# TT7D_v1_0.net
KiCad netlist of a schematic drawn in EAGLE
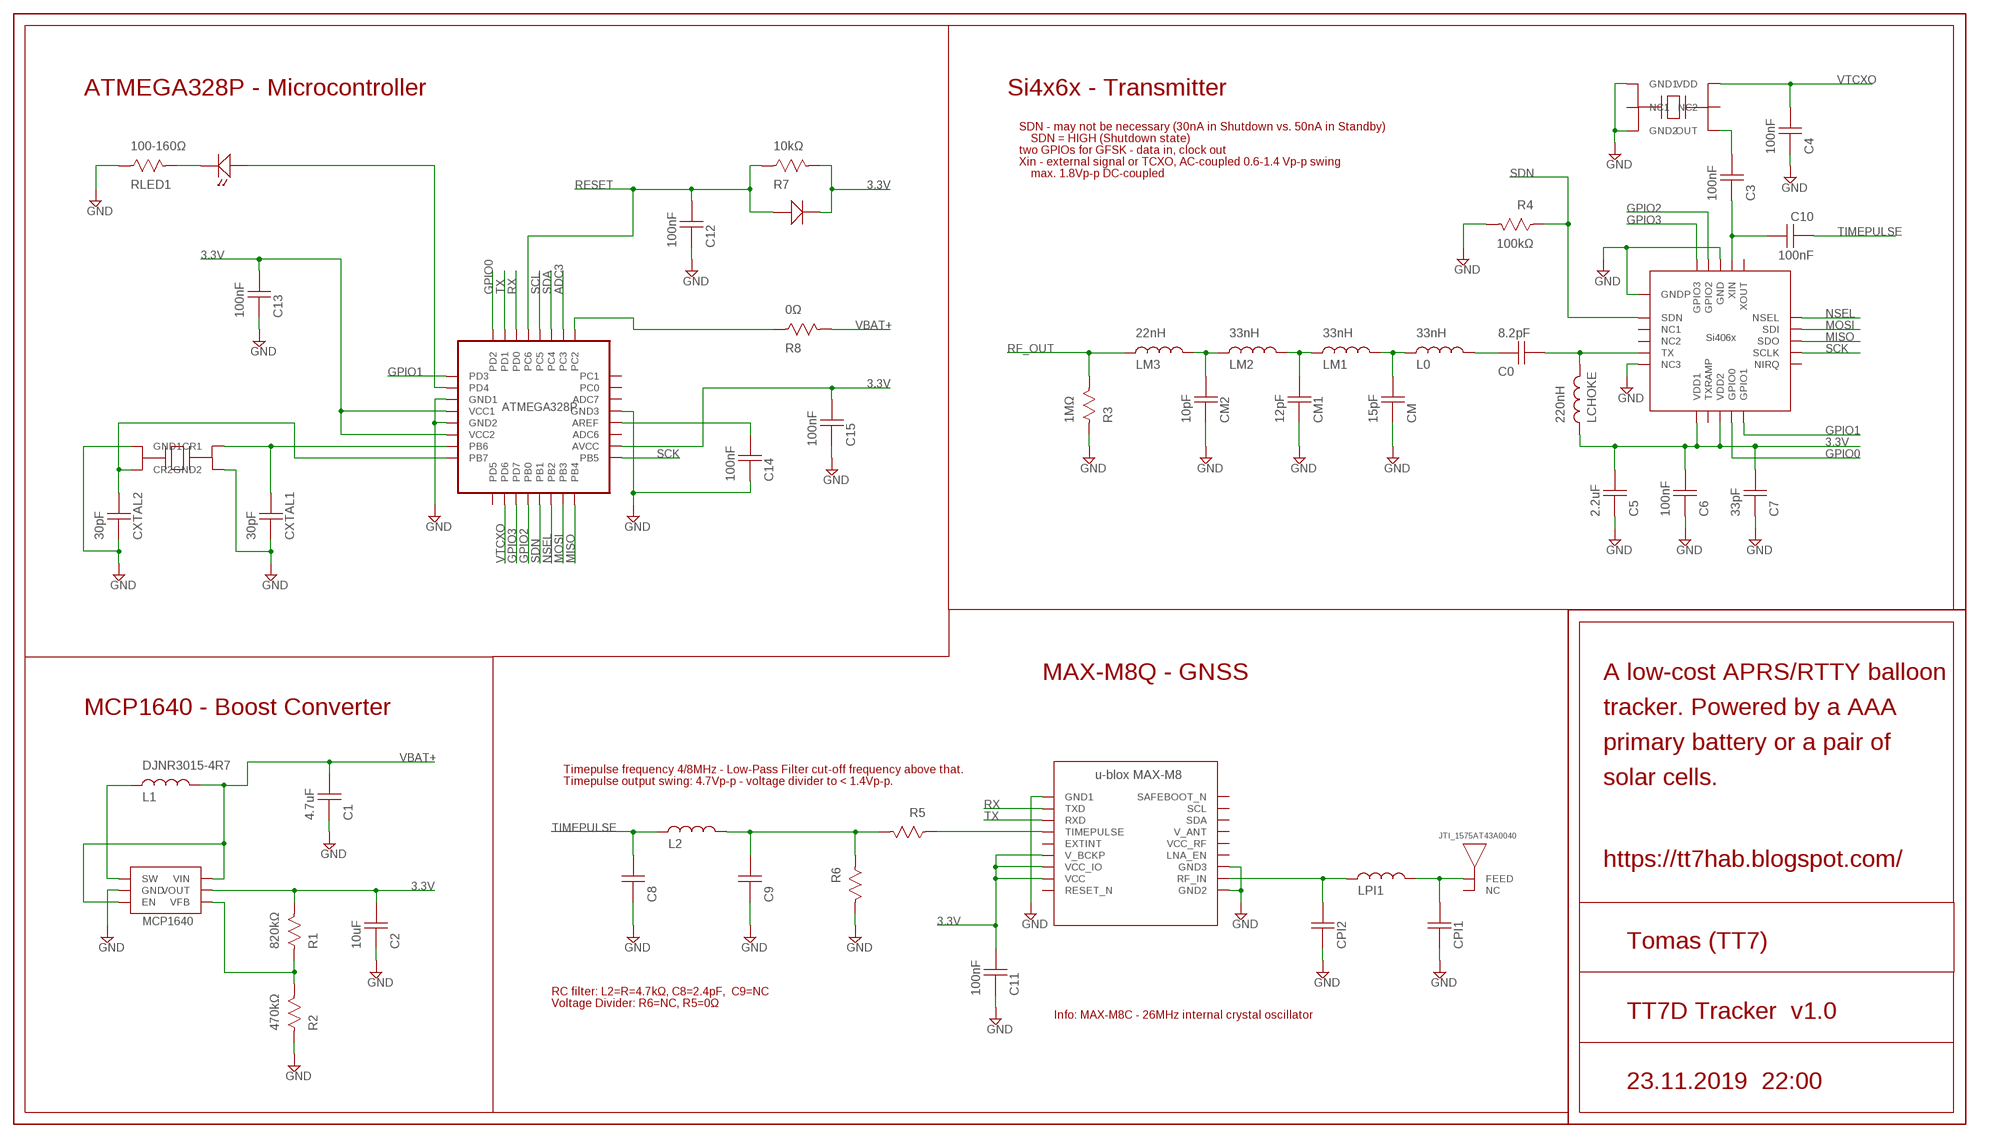
[diagram p0: schematic, sheet 1]

(export (version "E")
  (design (tool "Eeschema 10.0.6"))
  (components
    (comp (ref "ANT1")
      (value "JTI_1575AT43A0040")
      (footprint "eagle-import:JTI_1575AT43A0040")
      (libsource (lib "eagle-import") (part "JTI_1575AT43A0040"))
    )
    (comp (ref "C0")
      (value "8.2pF")
      (footprint "eagle-import:CAP0402")
      (libsource (lib "eagle-import") (part "CAP0402"))
    )
    (comp (ref "C1")
      (value "4.7uF")
      (footprint "eagle-import:CAP0402")
      (libsource (lib "eagle-import") (part "CAP0402"))
    )
    (comp (ref "C2")
      (value "10uF")
      (footprint "eagle-import:CAP0402")
      (libsource (lib "eagle-import") (part "CAP0402"))
    )
    (comp (ref "C3")
      (value "100nF")
      (footprint "eagle-import:CAP0402")
      (libsource (lib "eagle-import") (part "CAP0402"))
    )
    (comp (ref "C4")
      (value "100nF")
      (footprint "eagle-import:CAP0402")
      (libsource (lib "eagle-import") (part "CAP0402"))
    )
    (comp (ref "C5")
      (value "2.2uF")
      (footprint "eagle-import:CAP0402")
      (libsource (lib "eagle-import") (part "CAP0402"))
    )
    (comp (ref "C6")
      (value "100nF")
      (footprint "eagle-import:CAP0402")
      (libsource (lib "eagle-import") (part "CAP0402"))
    )
    (comp (ref "C7")
      (value "33pF")
      (footprint "eagle-import:CAP0402")
      (libsource (lib "eagle-import") (part "CAP0402"))
    )
    (comp (ref "C8")
      (value "CAP0402")
      (footprint "eagle-import:CAP0402")
      (libsource (lib "eagle-import") (part "CAP0402"))
    )
    (comp (ref "C9")
      (value "CAP0402")
      (footprint "eagle-import:CAP0402")
      (libsource (lib "eagle-import") (part "CAP0402"))
    )
    (comp (ref "C10")
      (value "100nF")
      (footprint "eagle-import:CAP0402")
      (libsource (lib "eagle-import") (part "CAP0402"))
    )
    (comp (ref "C11")
      (value "100nF")
      (footprint "eagle-import:CAP0402")
      (libsource (lib "eagle-import") (part "CAP0402"))
    )
    (comp (ref "C12")
      (value "100nF")
      (footprint "eagle-import:CAP0402")
      (libsource (lib "eagle-import") (part "CAP0402"))
    )
    (comp (ref "C13")
      (value "100nF")
      (footprint "eagle-import:CAP0402")
      (libsource (lib "eagle-import") (part "CAP0402"))
    )
    (comp (ref "C14")
      (value "100nF")
      (footprint "eagle-import:CAP0402")
      (libsource (lib "eagle-import") (part "CAP0402"))
    )
    (comp (ref "C15")
      (value "100nF")
      (footprint "eagle-import:CAP0402")
      (libsource (lib "eagle-import") (part "CAP0402"))
    )
    (comp (ref "CM")
      (value "15pF")
      (footprint "eagle-import:CAP0402")
      (libsource (lib "eagle-import") (part "CAP0402"))
    )
    (comp (ref "CM1")
      (value "12pF")
      (footprint "eagle-import:CAP0402")
      (libsource (lib "eagle-import") (part "CAP0402"))
    )
    (comp (ref "CM2")
      (value "10pF")
      (footprint "eagle-import:CAP0402")
      (libsource (lib "eagle-import") (part "CAP0402"))
    )
    (comp (ref "CPI1")
      (value "CAP0402")
      (footprint "eagle-import:CAP0402")
      (libsource (lib "eagle-import") (part "CAP0402"))
    )
    (comp (ref "CPI2")
      (value "CAP0402")
      (footprint "eagle-import:CAP0402")
      (libsource (lib "eagle-import") (part "CAP0402"))
    )
    (comp (ref "CXTAL1")
      (value "30pF")
      (footprint "eagle-import:CAP0402")
      (libsource (lib "eagle-import") (part "CAP0402"))
    )
    (comp (ref "CXTAL2")
      (value "30pF")
      (footprint "eagle-import:CAP0402")
      (libsource (lib "eagle-import") (part "CAP0402"))
    )
    (comp (ref "D1")
      (value "DIODE0402")
      (footprint "eagle-import:DIODE0402")
      (libsource (lib "eagle-import") (part "DIODE0402"))
    )
    (comp (ref "L0")
      (value "33nH")
      (footprint "eagle-import:IND0402")
      (libsource (lib "eagle-import") (part "IND0402"))
    )
    (comp (ref "L1")
      (value "DJNR3015-4R7")
      (footprint "eagle-import:DJNR3015")
      (libsource (lib "eagle-import") (part "DJNR3015"))
    )
    (comp (ref "L2")
      (value "IND0402")
      (footprint "eagle-import:IND0402")
      (libsource (lib "eagle-import") (part "IND0402"))
    )
    (comp (ref "LCHOKE")
      (value "220nH")
      (footprint "eagle-import:IND0402")
      (libsource (lib "eagle-import") (part "IND0402"))
    )
    (comp (ref "LED1")
      (value "LED0603")
      (footprint "eagle-import:LED0603")
      (libsource (lib "eagle-import") (part "LED0603"))
    )
    (comp (ref "LM1")
      (value "33nH")
      (footprint "eagle-import:IND0402")
      (libsource (lib "eagle-import") (part "IND0402"))
    )
    (comp (ref "LM2")
      (value "33nH")
      (footprint "eagle-import:IND0402")
      (libsource (lib "eagle-import") (part "IND0402"))
    )
    (comp (ref "LM3")
      (value "22nH")
      (footprint "eagle-import:IND0402")
      (libsource (lib "eagle-import") (part "IND0402"))
    )
    (comp (ref "LPI1")
      (value "IND0402")
      (footprint "eagle-import:IND0402")
      (libsource (lib "eagle-import") (part "IND0402"))
    )
    (comp (ref "R1")
      (value "820kΩ")
      (footprint "eagle-import:RES0402")
      (libsource (lib "eagle-import") (part "RES0402"))
    )
    (comp (ref "R2")
      (value "470kΩ")
      (footprint "eagle-import:RES0402")
      (libsource (lib "eagle-import") (part "RES0402"))
    )
    (comp (ref "R3")
      (value "1MΩ")
      (footprint "eagle-import:RES0402")
      (libsource (lib "eagle-import") (part "RES0402"))
    )
    (comp (ref "R4")
      (value "100kΩ")
      (footprint "eagle-import:RES0402")
      (libsource (lib "eagle-import") (part "RES0402"))
    )
    (comp (ref "R5")
      (value "RES0402")
      (footprint "eagle-import:RES0402")
      (libsource (lib "eagle-import") (part "RES0402"))
    )
    (comp (ref "R6")
      (value "RES0402")
      (footprint "eagle-import:RES0402")
      (libsource (lib "eagle-import") (part "RES0402"))
    )
    (comp (ref "R7")
      (value "10kΩ")
      (footprint "eagle-import:RES0402")
      (libsource (lib "eagle-import") (part "RES0402"))
    )
    (comp (ref "R8")
      (value "0Ω")
      (footprint "eagle-import:RES0402")
      (libsource (lib "eagle-import") (part "RES0402"))
    )
    (comp (ref "RLED1")
      (value "100-160Ω")
      (footprint "eagle-import:RES0402")
      (libsource (lib "eagle-import") (part "RES0402"))
    )
    (comp (ref "U1")
      (value "ATMEGA328P-AU")
      (footprint "eagle-import:ATMEGA328P-AU")
      (libsource (lib "eagle-import") (part "ATMEGA328P-AU"))
    )
    (comp (ref "U2")
      (value "UBLOX_MAX-7C")
      (footprint "eagle-import:UBLOX_MAX-7C")
      (libsource (lib "eagle-import") (part "UBLOX_MAX-7C"))
    )
    (comp (ref "U3")
      (value "SI406X")
      (footprint "eagle-import:SI406X")
      (libsource (lib "eagle-import") (part "SI406X"))
    )
    (comp (ref "U4")
      (value "IT3205CE_TCXO_6P")
      (footprint "eagle-import:IT3205CE_TCXO_6P")
      (libsource (lib "eagle-import") (part "IT3205CE_TCXO_6P"))
    )
    (comp (ref "U5")
      (value "MCP1640")
      (footprint "eagle-import:MCP1640")
      (libsource (lib "eagle-import") (part "MCP1640"))
    )
    (comp (ref "XTAL1")
      (value "LFXTAL055663")
      (footprint "eagle-import:LFXTAL055663")
      (libsource (lib "eagle-import") (part "LFXTAL055663"))
    )
  )
  (nets
    (net (code "1") (name "/3.3V") (class "Default")
      (node (ref "C11") (pin "P$2") (pinfunction "P$2_P$2") (pintype "bidirectional"))
      (node (ref "C13") (pin "P$2") (pinfunction "P$2_P$2") (pintype "bidirectional"))
      (node (ref "C15") (pin "P$2") (pinfunction "P$2_P$2") (pintype "bidirectional"))
      (node (ref "C2") (pin "P$2") (pinfunction "P$2_P$2") (pintype "bidirectional"))
      (node (ref "C5") (pin "P$2") (pinfunction "P$2_P$2") (pintype "bidirectional"))
      (node (ref "C6") (pin "P$2") (pinfunction "P$2_P$2") (pintype "bidirectional"))
      (node (ref "C7") (pin "P$2") (pinfunction "P$2_P$2") (pintype "bidirectional"))
      (node (ref "D1") (pin "CATHODE") (pinfunction "CATHODE_CATHODE") (pintype "bidirectional"))
      (node (ref "LCHOKE") (pin "P$1") (pinfunction "P$1_P$1") (pintype "bidirectional"))
      (node (ref "R1") (pin "P$2") (pinfunction "P$2_P$2") (pintype "bidirectional"))
      (node (ref "R7") (pin "P$2") (pinfunction "P$2_P$2") (pintype "bidirectional"))
      (node (ref "U1") (pin "AVCC") (pinfunction "AVCC_AVCC") (pintype "power_in"))
      (node (ref "U1") (pin "VCC1") (pinfunction "VCC1_VCC1") (pintype "power_in"))
      (node (ref "U1") (pin "VCC2") (pinfunction "VCC2_VCC2") (pintype "power_in"))
      (node (ref "U2") (pin "VCC") (pinfunction "VCC_VCC") (pintype "bidirectional"))
      (node (ref "U2") (pin "VCC_IO") (pinfunction "VCC_IO_VCC_IO") (pintype "bidirectional"))
      (node (ref "U2") (pin "V_BCKP") (pinfunction "V_BCKP_V_BCKP") (pintype "bidirectional"))
      (node (ref "U3") (pin "VDD1") (pinfunction "VDD1_VDD1") (pintype "bidirectional"))
      (node (ref "U3") (pin "VDD2") (pinfunction "VDD2_VDD2") (pintype "bidirectional"))
      (node (ref "U5") (pin "VOUT") (pinfunction "VOUT_VOUT") (pintype "bidirectional"))
    )
    (net (code "2") (name "/ADC3") (class "Default")
      (node (ref "U1") (pin "PC3") (pinfunction "PC3_PC3") (pintype "bidirectional"))
    )
    (net (code "3") (name "/GPIO0") (class "Default")
      (node (ref "U1") (pin "PD2") (pinfunction "PD2_PD2") (pintype "bidirectional"))
      (node (ref "U3") (pin "GPIO0") (pinfunction "GPIO0_GPIO0") (pintype "bidirectional"))
    )
    (net (code "4") (name "/GPIO1") (class "Default")
      (node (ref "U1") (pin "PD3") (pinfunction "PD3_PD3") (pintype "bidirectional"))
      (node (ref "U3") (pin "GPIO1") (pinfunction "GPIO1_GPIO1") (pintype "bidirectional"))
    )
    (net (code "5") (name "/GPIO2") (class "Default")
      (node (ref "U1") (pin "PB0") (pinfunction "PB0_PB0") (pintype "bidirectional"))
      (node (ref "U3") (pin "GPIO2") (pinfunction "GPIO2_GPIO2") (pintype "bidirectional"))
    )
    (net (code "6") (name "/GPIO3") (class "Default")
      (node (ref "U1") (pin "PD7") (pinfunction "PD7_PD7") (pintype "bidirectional"))
      (node (ref "U3") (pin "GPIO3") (pinfunction "GPIO3_GPIO3") (pintype "bidirectional"))
    )
    (net (code "7") (name "/MISO") (class "Default")
      (node (ref "U1") (pin "PB4") (pinfunction "PB4_PB4") (pintype "bidirectional"))
      (node (ref "U3") (pin "SDO") (pinfunction "SDO_SDO") (pintype "bidirectional"))
    )
    (net (code "8") (name "/MOSI") (class "Default")
      (node (ref "U1") (pin "PB3") (pinfunction "PB3_PB3") (pintype "bidirectional"))
      (node (ref "U3") (pin "SDI") (pinfunction "SDI_SDI") (pintype "bidirectional"))
    )
    (net (code "9") (name "/NSEL") (class "Default")
      (node (ref "U1") (pin "PB2") (pinfunction "PB2_PB2") (pintype "bidirectional"))
      (node (ref "U3") (pin "NSEL") (pinfunction "NSEL_NSEL") (pintype "bidirectional"))
    )
    (net (code "10") (name "/RESET") (class "Default")
      (node (ref "C12") (pin "P$2") (pinfunction "P$2_P$2") (pintype "bidirectional"))
      (node (ref "D1") (pin "ANODE") (pinfunction "ANODE_ANODE") (pintype "bidirectional"))
      (node (ref "R7") (pin "P$1") (pinfunction "P$1_P$1") (pintype "bidirectional"))
      (node (ref "U1") (pin "PC6") (pinfunction "PC6_PC6") (pintype "bidirectional"))
    )
    (net (code "11") (name "/RF_OUT") (class "Default")
      (node (ref "LM3") (pin "P$1") (pinfunction "P$1_P$1") (pintype "bidirectional"))
      (node (ref "R3") (pin "P$2") (pinfunction "P$2_P$2") (pintype "bidirectional"))
    )
    (net (code "12") (name "/RX") (class "Default")
      (node (ref "U1") (pin "PD0") (pinfunction "PD0_PD0") (pintype "bidirectional"))
      (node (ref "U2") (pin "TXD") (pinfunction "TXD_TXD") (pintype "bidirectional"))
    )
    (net (code "13") (name "/SCK") (class "Default")
      (node (ref "U1") (pin "PB5") (pinfunction "PB5_PB5") (pintype "bidirectional"))
      (node (ref "U3") (pin "SCLK") (pinfunction "SCLK_SCLK") (pintype "bidirectional"))
    )
    (net (code "14") (name "/SCL") (class "Default")
      (node (ref "U1") (pin "PC5") (pinfunction "PC5_PC5") (pintype "bidirectional"))
    )
    (net (code "15") (name "/SDA") (class "Default")
      (node (ref "U1") (pin "PC4") (pinfunction "PC4_PC4") (pintype "bidirectional"))
    )
    (net (code "16") (name "/SDN") (class "Default")
      (node (ref "R4") (pin "P$1") (pinfunction "P$1_P$1") (pintype "bidirectional"))
      (node (ref "U1") (pin "PB1") (pinfunction "PB1_PB1") (pintype "bidirectional"))
      (node (ref "U3") (pin "SDN") (pinfunction "SDN_SDN") (pintype "bidirectional"))
    )
    (net (code "17") (name "/TIMEPULSE") (class "Default")
      (node (ref "C10") (pin "P$1") (pinfunction "P$1_P$1") (pintype "bidirectional"))
      (node (ref "C8") (pin "P$2") (pinfunction "P$2_P$2") (pintype "bidirectional"))
      (node (ref "L2") (pin "P$1") (pinfunction "P$1_P$1") (pintype "bidirectional"))
    )
    (net (code "18") (name "/TX") (class "Default")
      (node (ref "U1") (pin "PD1") (pinfunction "PD1_PD1") (pintype "bidirectional"))
      (node (ref "U2") (pin "RXD") (pinfunction "RXD_RXD") (pintype "bidirectional"))
    )
    (net (code "19") (name "/VBAT+") (class "Default")
      (node (ref "C1") (pin "P$2") (pinfunction "P$2_P$2") (pintype "bidirectional"))
      (node (ref "L1") (pin "P2") (pinfunction "P$2_P2") (pintype "bidirectional"))
      (node (ref "R8") (pin "P$2") (pinfunction "P$2_P$2") (pintype "bidirectional"))
      (node (ref "U5") (pin "EN") (pinfunction "EN_EN") (pintype "input"))
      (node (ref "U5") (pin "VIN") (pinfunction "VIN_VIN") (pintype "bidirectional"))
    )
    (net (code "20") (name "/VTCXO") (class "Default")
      (node (ref "C4") (pin "P$2") (pinfunction "P$2_P$2") (pintype "bidirectional"))
      (node (ref "U1") (pin "PD6") (pinfunction "PD6_PD6") (pintype "bidirectional"))
      (node (ref "U4") (pin "VDD") (pinfunction "VDD_VDD") (pintype "bidirectional"))
    )
    (net (code "21") (name "GND") (class "Default")
      (node (ref "C1") (pin "P$1") (pinfunction "P$1_P$1") (pintype "bidirectional"))
      (node (ref "C11") (pin "P$1") (pinfunction "P$1_P$1") (pintype "bidirectional"))
      (node (ref "C12") (pin "P$1") (pinfunction "P$1_P$1") (pintype "bidirectional"))
      (node (ref "C13") (pin "P$1") (pinfunction "P$1_P$1") (pintype "bidirectional"))
      (node (ref "C14") (pin "P$1") (pinfunction "P$1_P$1") (pintype "bidirectional"))
      (node (ref "C15") (pin "P$1") (pinfunction "P$1_P$1") (pintype "bidirectional"))
      (node (ref "C2") (pin "P$1") (pinfunction "P$1_P$1") (pintype "bidirectional"))
      (node (ref "C4") (pin "P$1") (pinfunction "P$1_P$1") (pintype "bidirectional"))
      (node (ref "C5") (pin "P$1") (pinfunction "P$1_P$1") (pintype "bidirectional"))
      (node (ref "C6") (pin "P$1") (pinfunction "P$1_P$1") (pintype "bidirectional"))
      (node (ref "C7") (pin "P$1") (pinfunction "P$1_P$1") (pintype "bidirectional"))
      (node (ref "C8") (pin "P$1") (pinfunction "P$1_P$1") (pintype "bidirectional"))
      (node (ref "C9") (pin "P$1") (pinfunction "P$1_P$1") (pintype "bidirectional"))
      (node (ref "CM") (pin "P$1") (pinfunction "P$1_P$1") (pintype "bidirectional"))
      (node (ref "CM1") (pin "P$1") (pinfunction "P$1_P$1") (pintype "bidirectional"))
      (node (ref "CM2") (pin "P$1") (pinfunction "P$1_P$1") (pintype "bidirectional"))
      (node (ref "CPI1") (pin "P$1") (pinfunction "P$1_P$1") (pintype "bidirectional"))
      (node (ref "CPI2") (pin "P$1") (pinfunction "P$1_P$1") (pintype "bidirectional"))
      (node (ref "CXTAL1") (pin "P$1") (pinfunction "P$1_P$1") (pintype "bidirectional"))
      (node (ref "CXTAL2") (pin "P$1") (pinfunction "P$1_P$1") (pintype "bidirectional"))
      (node (ref "R2") (pin "P$1") (pinfunction "P$1_P$1") (pintype "bidirectional"))
      (node (ref "R3") (pin "P$1") (pinfunction "P$1_P$1") (pintype "bidirectional"))
      (node (ref "R4") (pin "P$2") (pinfunction "P$2_P$2") (pintype "bidirectional"))
      (node (ref "R6") (pin "P$2") (pinfunction "P$2_P$2") (pintype "bidirectional"))
      (node (ref "RLED1") (pin "P$1") (pinfunction "P$1_P$1") (pintype "bidirectional"))
      (node (ref "U1") (pin "GND1") (pinfunction "GND1_GND1") (pintype "passive"))
      (node (ref "U1") (pin "GND2") (pinfunction "GND2_GND2") (pintype "passive"))
      (node (ref "U1") (pin "GND3") (pinfunction "GND3_GND3") (pintype "passive"))
      (node (ref "U2") (pin "GND1") (pinfunction "GND1_GND1") (pintype "bidirectional"))
      (node (ref "U2") (pin "GND2") (pinfunction "GND2_GND2") (pintype "bidirectional"))
      (node (ref "U2") (pin "GND3") (pinfunction "GND3_GND3") (pintype "bidirectional"))
      (node (ref "U3") (pin "GND") (pinfunction "GND_GND") (pintype "bidirectional"))
      (node (ref "U3") (pin "GNDP") (pinfunction "GNDP_GNDP") (pintype "bidirectional"))
      (node (ref "U3") (pin "NC3") (pinfunction "NC3_NC3") (pintype "bidirectional"))
      (node (ref "U4") (pin "GND1") (pinfunction "GND1_GND1") (pintype "bidirectional"))
      (node (ref "U4") (pin "GND2") (pinfunction "GND2_GND2") (pintype "bidirectional"))
      (node (ref "U5") (pin "GND") (pinfunction "GND_GND") (pintype "bidirectional"))
      (node (ref "XTAL1") (pin "GND1") (pinfunction "GND1_GND1") (pintype "bidirectional"))
      (node (ref "XTAL1") (pin "GND2") (pinfunction "GND2_GND2") (pintype "bidirectional"))
    )
    (net (code "22") (name "Net-(ANT1-PadFEED)") (class "Default")
      (node (ref "ANT1") (pin "FEED") (pinfunction "FEED_FEED") (pintype "bidirectional"))
      (node (ref "CPI1") (pin "P$2") (pinfunction "P$2_P$2") (pintype "bidirectional"))
      (node (ref "LPI1") (pin "P$2") (pinfunction "P$2_P$2") (pintype "bidirectional"))
    )
    (net (code "23") (name "Net-(C0-PadP$1)") (class "Default")
      (node (ref "C0") (pin "P$1") (pinfunction "P$1_P$1") (pintype "bidirectional"))
      (node (ref "L0") (pin "P$2") (pinfunction "P$2_P$2") (pintype "bidirectional"))
    )
    (net (code "24") (name "Net-(C0-PadP$2)") (class "Default")
      (node (ref "C0") (pin "P$2") (pinfunction "P$2_P$2") (pintype "bidirectional"))
      (node (ref "LCHOKE") (pin "P$2") (pinfunction "P$2_P$2") (pintype "bidirectional"))
      (node (ref "U3") (pin "TX") (pinfunction "TX_TX") (pintype "bidirectional"))
    )
    (net (code "25") (name "Net-(C3-PadP$2)") (class "Default")
      (node (ref "C3") (pin "P$2") (pinfunction "P$2_P$2") (pintype "bidirectional"))
      (node (ref "U4") (pin "OUT") (pinfunction "OUT_OUT") (pintype "bidirectional"))
    )
    (net (code "26") (name "Net-(C9-PadP$2)") (class "Default")
      (node (ref "C9") (pin "P$2") (pinfunction "P$2_P$2") (pintype "bidirectional"))
      (node (ref "L2") (pin "P$2") (pinfunction "P$2_P$2") (pintype "bidirectional"))
      (node (ref "R5") (pin "P$2") (pinfunction "P$2_P$2") (pintype "bidirectional"))
      (node (ref "R6") (pin "P$1") (pinfunction "P$1_P$1") (pintype "bidirectional"))
    )
    (net (code "27") (name "Net-(C10-PadP$2)") (class "Default")
      (node (ref "C10") (pin "P$2") (pinfunction "P$2_P$2") (pintype "bidirectional"))
      (node (ref "C3") (pin "P$1") (pinfunction "P$1_P$1") (pintype "bidirectional"))
      (node (ref "U3") (pin "XIN") (pinfunction "XIN_XIN") (pintype "bidirectional"))
    )
    (net (code "28") (name "Net-(C14-PadP$2)") (class "Default")
      (node (ref "C14") (pin "P$2") (pinfunction "P$2_P$2") (pintype "bidirectional"))
      (node (ref "U1") (pin "AREF") (pinfunction "AREF_AREF") (pintype "input"))
    )
    (net (code "29") (name "Net-(CM-PadP$2)") (class "Default")
      (node (ref "CM") (pin "P$2") (pinfunction "P$2_P$2") (pintype "bidirectional"))
      (node (ref "L0") (pin "P$1") (pinfunction "P$1_P$1") (pintype "bidirectional"))
      (node (ref "LM1") (pin "P$2") (pinfunction "P$2_P$2") (pintype "bidirectional"))
    )
    (net (code "30") (name "Net-(CM1-PadP$2)") (class "Default")
      (node (ref "CM1") (pin "P$2") (pinfunction "P$2_P$2") (pintype "bidirectional"))
      (node (ref "LM1") (pin "P$1") (pinfunction "P$1_P$1") (pintype "bidirectional"))
      (node (ref "LM2") (pin "P$2") (pinfunction "P$2_P$2") (pintype "bidirectional"))
    )
    (net (code "31") (name "Net-(CM2-PadP$2)") (class "Default")
      (node (ref "CM2") (pin "P$2") (pinfunction "P$2_P$2") (pintype "bidirectional"))
      (node (ref "LM2") (pin "P$1") (pinfunction "P$1_P$1") (pintype "bidirectional"))
      (node (ref "LM3") (pin "P$2") (pinfunction "P$2_P$2") (pintype "bidirectional"))
    )
    (net (code "32") (name "Net-(CPI2-PadP$2)") (class "Default")
      (node (ref "CPI2") (pin "P$2") (pinfunction "P$2_P$2") (pintype "bidirectional"))
      (node (ref "LPI1") (pin "P$1") (pinfunction "P$1_P$1") (pintype "bidirectional"))
      (node (ref "U2") (pin "RF_IN") (pinfunction "RF_IN_RF_IN") (pintype "bidirectional"))
    )
    (net (code "33") (name "Net-(L1-P$1)") (class "Default")
      (node (ref "L1") (pin "P1") (pinfunction "P$1_P1") (pintype "bidirectional"))
      (node (ref "U5") (pin "SW") (pinfunction "SW_SW") (pintype "bidirectional"))
    )
    (net (code "34") (name "Net-(LED1-PadANODE)") (class "Default")
      (node (ref "LED1") (pin "ANODE") (pinfunction "ANODE_ANODE") (pintype "bidirectional"))
      (node (ref "U1") (pin "PD4") (pinfunction "PD4_PD4") (pintype "bidirectional"))
    )
    (net (code "35") (name "Net-(LED1-PadCATHODE)") (class "Default")
      (node (ref "LED1") (pin "CATHODE") (pinfunction "CATHODE_CATHODE") (pintype "bidirectional"))
      (node (ref "RLED1") (pin "P$2") (pinfunction "P$2_P$2") (pintype "bidirectional"))
    )
    (net (code "36") (name "Net-(R1-PadP$1)") (class "Default")
      (node (ref "R1") (pin "P$1") (pinfunction "P$1_P$1") (pintype "bidirectional"))
      (node (ref "R2") (pin "P$2") (pinfunction "P$2_P$2") (pintype "bidirectional"))
      (node (ref "U5") (pin "VFB") (pinfunction "VFB_VFB") (pintype "bidirectional"))
    )
    (net (code "37") (name "Net-(R5-PadP$1)") (class "Default")
      (node (ref "R5") (pin "P$1") (pinfunction "P$1_P$1") (pintype "bidirectional"))
      (node (ref "U2") (pin "TIMEPULSE") (pinfunction "TIMEPULSE_TIMEPULSE") (pintype "bidirectional"))
    )
    (net (code "38") (name "Net-(R8-PadP$1)") (class "Default")
      (node (ref "R8") (pin "P$1") (pinfunction "P$1_P$1") (pintype "bidirectional"))
      (node (ref "U1") (pin "PC2") (pinfunction "PC2_PC2") (pintype "bidirectional"))
    )
    (net (code "39") (name "Net-(XTAL1-CR1)") (class "Default")
      (node (ref "CXTAL1") (pin "P$2") (pinfunction "P$2_P$2") (pintype "bidirectional"))
      (node (ref "U1") (pin "PB6") (pinfunction "PB6_PB6") (pintype "bidirectional"))
      (node (ref "XTAL1") (pin "CRYSTAL1") (pinfunction "CR1_CRYSTAL1") (pintype "bidirectional"))
    )
    (net (code "40") (name "Net-(XTAL1-CR2)") (class "Default")
      (node (ref "CXTAL2") (pin "P$2") (pinfunction "P$2_P$2") (pintype "bidirectional"))
      (node (ref "U1") (pin "PB7") (pinfunction "PB7_PB7") (pintype "bidirectional"))
      (node (ref "XTAL1") (pin "CRYSTAL2") (pinfunction "CR2_CRYSTAL2") (pintype "bidirectional"))
    )
    (net (code "41") (name "unconnected-(ANT1-PadNC)") (class "Default")
      (node (ref "ANT1") (pin "NC") (pinfunction "NC_NC") (pintype "bidirectional"))
    )
    (net (code "42") (name "unconnected-(U1-PadADC6)") (class "Default")
      (node (ref "U1") (pin "ADC6") (pinfunction "ADC6_ADC6") (pintype "input"))
    )
    (net (code "43") (name "unconnected-(U1-PadADC7)") (class "Default")
      (node (ref "U1") (pin "ADC7") (pinfunction "ADC7_ADC7") (pintype "input"))
    )
    (net (code "44") (name "unconnected-(U1-PadPC0)") (class "Default")
      (node (ref "U1") (pin "PC0") (pinfunction "PC0_PC0") (pintype "bidirectional"))
    )
    (net (code "45") (name "unconnected-(U1-PadPC1)") (class "Default")
      (node (ref "U1") (pin "PC1") (pinfunction "PC1_PC1") (pintype "bidirectional"))
    )
    (net (code "46") (name "unconnected-(U1-PadPD5)") (class "Default")
      (node (ref "U1") (pin "PD5") (pinfunction "PD5_PD5") (pintype "bidirectional"))
    )
    (net (code "47") (name "unconnected-(U2-PadEXTINT)") (class "Default")
      (node (ref "U2") (pin "EXTINT") (pinfunction "EXTINT_EXTINT") (pintype "bidirectional"))
    )
    (net (code "48") (name "unconnected-(U2-PadLNA_EN)") (class "Default")
      (node (ref "U2") (pin "LNA_EN") (pinfunction "LNA_EN_LNA_EN") (pintype "bidirectional"))
    )
    (net (code "49") (name "unconnected-(U2-PadRESET_N)") (class "Default")
      (node (ref "U2") (pin "RESET_N") (pinfunction "RESET_N_RESET_N") (pintype "bidirectional"))
    )
    (net (code "50") (name "unconnected-(U2-PadSAFEBOOT_N)") (class "Default")
      (node (ref "U2") (pin "SAFEBOOT_N") (pinfunction "SAFEBOOT_N_SAFEBOOT_N") (pintype "bidirectional"))
    )
    (net (code "51") (name "unconnected-(U2-PadSCL)") (class "Default")
      (node (ref "U2") (pin "SCL") (pinfunction "SCL_SCL") (pintype "bidirectional"))
    )
    (net (code "52") (name "unconnected-(U2-PadSDA)") (class "Default")
      (node (ref "U2") (pin "SDA") (pinfunction "SDA_SDA") (pintype "bidirectional"))
    )
    (net (code "53") (name "unconnected-(U2-PadVCC_RF)") (class "Default")
      (node (ref "U2") (pin "VCC_RF") (pinfunction "VCC_RF_VCC_RF") (pintype "bidirectional"))
    )
    (net (code "54") (name "unconnected-(U2-PadV_ANT)") (class "Default")
      (node (ref "U2") (pin "V_ANT") (pinfunction "V_ANT_V_ANT") (pintype "bidirectional"))
    )
    (net (code "55") (name "unconnected-(U3-PadNC1)") (class "Default")
      (node (ref "U3") (pin "NC1") (pinfunction "NC1_NC1") (pintype "bidirectional"))
    )
    (net (code "56") (name "unconnected-(U3-PadNC2)") (class "Default")
      (node (ref "U3") (pin "NC2") (pinfunction "NC2_NC2") (pintype "bidirectional"))
    )
    (net (code "57") (name "unconnected-(U3-PadNIRQ)") (class "Default")
      (node (ref "U3") (pin "NIRQ") (pinfunction "NIRQ_NIRQ") (pintype "bidirectional"))
    )
    (net (code "58") (name "unconnected-(U3-PadTXRAMP)") (class "Default")
      (node (ref "U3") (pin "TXRAMP") (pinfunction "TXRAMP_TXRAMP") (pintype "bidirectional"))
    )
    (net (code "59") (name "unconnected-(U3-PadXOUT)") (class "Default")
      (node (ref "U3") (pin "XOUT") (pinfunction "XOUT_XOUT") (pintype "bidirectional"))
    )
    (net (code "60") (name "unconnected-(U4-PadNC1)") (class "Default")
      (node (ref "U4") (pin "NC1") (pinfunction "NC1_NC1") (pintype "bidirectional"))
    )
    (net (code "61") (name "unconnected-(U4-PadNC2)") (class "Default")
      (node (ref "U4") (pin "NC2") (pinfunction "NC2_NC2") (pintype "bidirectional"))
    )
  )
)
